# Top.net
KiCad netlist of a schematic drawn in Altium Designer
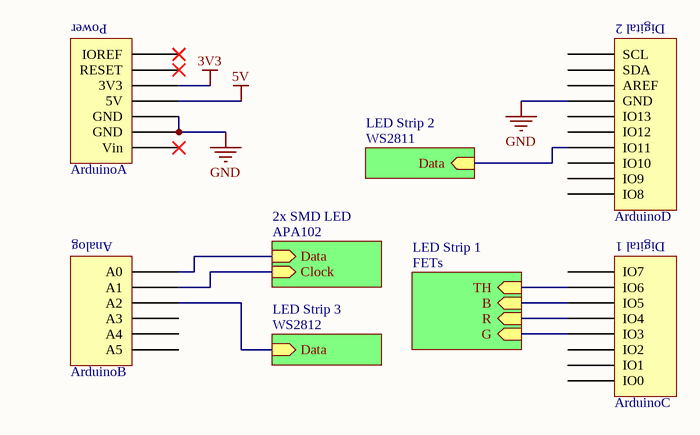
[diagram p0: Top.SchDoc]

(export (version "E")
  (design (tool "Eeschema 10.0.6"))
  (components
    (comp (ref "Arduino")
      (value "Uno")
      (footprint "Arduino Uno")
      (libsource (lib "Arduino") (part "Arduino Uno"))
    )
  )
  (nets
    (net (code "1") (name "/B") (class "Default")
      (node (ref "Arduino") (pin "5") (pinfunction "IO5_5") (pintype "passive"))
    )
    (net (code "2") (name "/Clock") (class "Default")
      (node (ref "Arduino") (pin "A1") (pinfunction "A1_A1") (pintype "passive"))
    )
    (net (code "3") (name "/Data") (class "Default")
      (node (ref "Arduino") (pin "11") (pinfunction "IO11_11") (pintype "passive"))
    )
    (net (code "4") (name "/Data_1") (class "Default")
      (node (ref "Arduino") (pin "A2") (pinfunction "A2_A2") (pintype "passive"))
    )
    (net (code "5") (name "/Data_2") (class "Default")
      (node (ref "Arduino") (pin "A0") (pinfunction "A0_A0") (pintype "passive"))
    )
    (net (code "6") (name "/G") (class "Default")
      (node (ref "Arduino") (pin "3") (pinfunction "IO3_3") (pintype "passive"))
    )
    (net (code "7") (name "/R") (class "Default")
      (node (ref "Arduino") (pin "4") (pinfunction "IO4_4") (pintype "passive"))
    )
    (net (code "8") (name "/TH") (class "Default")
      (node (ref "Arduino") (pin "6") (pinfunction "IO6_6") (pintype "passive"))
    )
    (net (code "9") (name "3V3") (class "Default")
      (node (ref "Arduino") (pin "3V3") (pinfunction "3V3_3V3") (pintype "passive"))
    )
    (net (code "10") (name "5V") (class "Default")
      (node (ref "Arduino") (pin "5V") (pinfunction "5V_5V") (pintype "passive"))
    )
    (net (code "11") (name "GND") (class "Default")
      (node (ref "Arduino") (pin "GND1") (pinfunction "GND_GND1") (pintype "passive"))
      (node (ref "Arduino") (pin "GND2") (pinfunction "GND_GND2") (pintype "passive"))
      (node (ref "Arduino") (pin "GND3") (pinfunction "GND_GND3") (pintype "passive"))
    )
    (net (code "12") (name "unconnected-(Arduino-PadA3)") (class "Default")
      (node (ref "Arduino") (pin "A3") (pinfunction "A3_A3") (pintype "passive"))
    )
    (net (code "13") (name "unconnected-(Arduino-PadA4)") (class "Default")
      (node (ref "Arduino") (pin "A4") (pinfunction "A4_A4") (pintype "passive"))
    )
    (net (code "14") (name "unconnected-(Arduino-PadA5)") (class "Default")
      (node (ref "Arduino") (pin "A5") (pinfunction "A5_A5") (pintype "passive"))
    )
    (net (code "15") (name "unconnected-(Arduino-PadAREF)") (class "Default")
      (node (ref "Arduino") (pin "AREF") (pinfunction "AREF_AREF") (pintype "passive"))
    )
    (net (code "16") (name "unconnected-(Arduino-PadIOREF)") (class "Default")
      (node (ref "Arduino") (pin "IOREF") (pinfunction "IOREF_IOREF") (pintype "passive+no_connect"))
    )
    (net (code "17") (name "unconnected-(Arduino-PadRESET)") (class "Default")
      (node (ref "Arduino") (pin "RESET") (pinfunction "RESET_RESET") (pintype "passive+no_connect"))
    )
    (net (code "18") (name "unconnected-(Arduino-PadSCL)") (class "Default")
      (node (ref "Arduino") (pin "SCL") (pinfunction "SCL_SCL") (pintype "passive"))
    )
    (net (code "19") (name "unconnected-(Arduino-PadSDA)") (class "Default")
      (node (ref "Arduino") (pin "SDA") (pinfunction "SDA_SDA") (pintype "passive"))
    )
    (net (code "20") (name "unconnected-(Arduino-PadVin)") (class "Default")
      (node (ref "Arduino") (pin "Vin") (pinfunction "Vin_Vin") (pintype "passive+no_connect"))
    )
    (net (code "21") (name "unconnected-(ArduinoC-IO0-Pad0)") (class "Default")
      (node (ref "Arduino") (pin "0") (pinfunction "IO0_0") (pintype "passive"))
    )
    (net (code "22") (name "unconnected-(ArduinoC-IO1-Pad1)") (class "Default")
      (node (ref "Arduino") (pin "1") (pinfunction "IO1_1") (pintype "passive"))
    )
    (net (code "23") (name "unconnected-(ArduinoC-IO2-Pad2)") (class "Default")
      (node (ref "Arduino") (pin "2") (pinfunction "IO2_2") (pintype "passive"))
    )
    (net (code "24") (name "unconnected-(ArduinoC-IO7-Pad7)") (class "Default")
      (node (ref "Arduino") (pin "7") (pinfunction "IO7_7") (pintype "passive"))
    )
    (net (code "25") (name "unconnected-(ArduinoD-IO8-Pad8)") (class "Default")
      (node (ref "Arduino") (pin "8") (pinfunction "IO8_8") (pintype "passive"))
    )
    (net (code "26") (name "unconnected-(ArduinoD-IO9-Pad9)") (class "Default")
      (node (ref "Arduino") (pin "9") (pinfunction "IO9_9") (pintype "passive"))
    )
    (net (code "27") (name "unconnected-(ArduinoD-IO10-Pad10)") (class "Default")
      (node (ref "Arduino") (pin "10") (pinfunction "IO10_10") (pintype "passive"))
    )
    (net (code "28") (name "unconnected-(ArduinoD-IO12-Pad12)") (class "Default")
      (node (ref "Arduino") (pin "12") (pinfunction "IO12_12") (pintype "passive"))
    )
    (net (code "29") (name "unconnected-(ArduinoD-IO13-Pad13)") (class "Default")
      (node (ref "Arduino") (pin "13") (pinfunction "IO13_13") (pintype "passive"))
    )
  )
)
